# Audio.net
KiCad netlist of a schematic drawn in Altium Designer
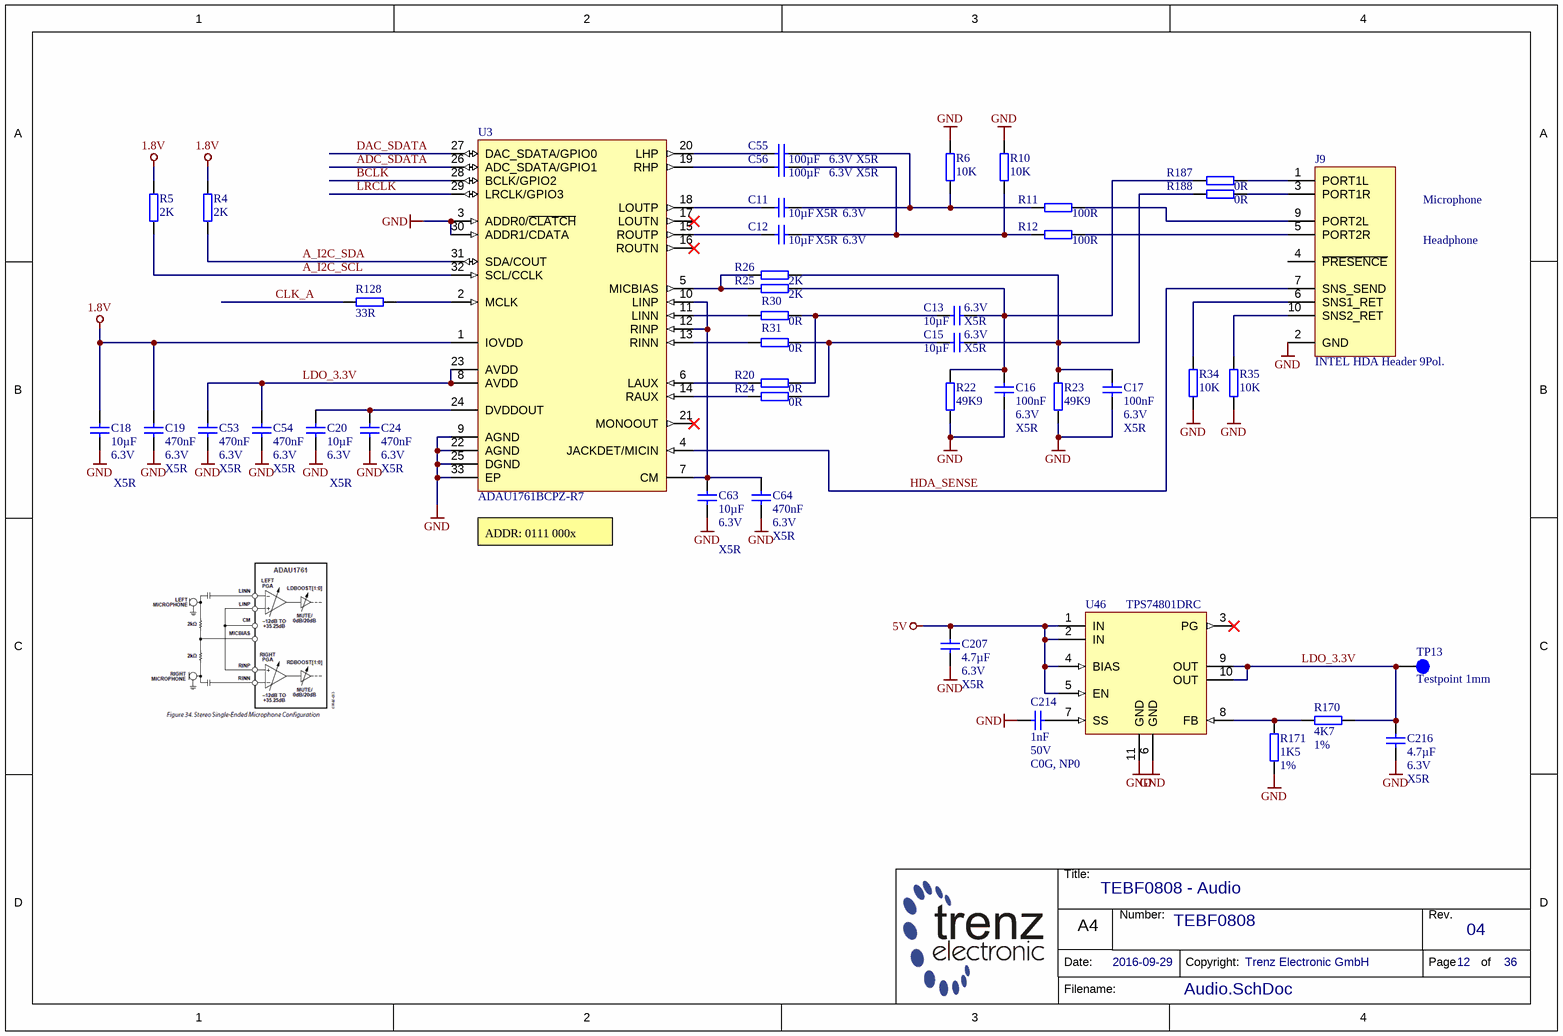
[diagram p0: Audio.SchDoc]

(export (version "E")
  (design (tool "Eeschema 10.0.6"))
  (components
    (comp (ref "C11")
      (value "10µF")
      (footprint "CAPC1608X90N")
      (description "KON 10µF 6,3V X5R SMD")
      (fields (field (name "VOLTAGE") "6.3V") (field (name "TECHNOLOGY") "X5R"))
      (libsource (lib "TE") (part "CAP-NP"))
    )
    (comp (ref "C12")
      (value "10µF")
      (footprint "CAPC1608X90N")
      (description "KON 10µF 6,3V X5R SMD")
      (fields (field (name "VOLTAGE") "6.3V") (field (name "TECHNOLOGY") "X5R"))
      (libsource (lib "TE") (part "CAP-NP"))
    )
    (comp (ref "C13")
      (value "10µF")
      (footprint "CAPC1608X90N")
      (description "KON 10µF 6,3V X5R SMD")
      (fields (field (name "VOLTAGE") "6.3V") (field (name "TECHNOLOGY") "X5R"))
      (libsource (lib "TE") (part "CAP-NP"))
    )
    (comp (ref "C15")
      (value "10µF")
      (footprint "CAPC1608X90N")
      (description "KON 10µF 6,3V X5R SMD")
      (fields (field (name "VOLTAGE") "6.3V") (field (name "TECHNOLOGY") "X5R"))
      (libsource (lib "TE") (part "CAP-NP"))
    )
    (comp (ref "C16")
      (value "100nF")
      (footprint "CAPC0603X33N")
      (description "KON 100nF 6.3V X5R SMD 10%")
      (fields
        (field (name "VOLTAGE") "6.3V")
        (field (name "TECHNOLOGY") "X5R")
        (field (name "TOLERANCE") "10%")
      )
      (libsource (lib "TE") (part "CAP-NP"))
    )
    (comp (ref "C17")
      (value "100nF")
      (footprint "CAPC0603X33N")
      (description "KON 100nF 6.3V X5R SMD 10%")
      (fields
        (field (name "VOLTAGE") "6.3V")
        (field (name "TECHNOLOGY") "X5R")
        (field (name "TOLERANCE") "10%")
      )
      (libsource (lib "TE") (part "CAP-NP"))
    )
    (comp (ref "C18")
      (value "10µF")
      (footprint "CAPC1608X90N")
      (description "KON 10µF 6,3V X5R SMD")
      (fields (field (name "VOLTAGE") "6.3V") (field (name "TECHNOLOGY") "X5R"))
      (libsource (lib "TE") (part "CAP-NP"))
    )
    (comp (ref "C19")
      (value "470nF")
      (footprint "CAPC1005X55N")
      (description "KON 470nF 6,3V X5R SMD")
      (fields (field (name "VOLTAGE") "6.3V") (field (name "TECHNOLOGY") "X5R"))
      (libsource (lib "TE") (part "CAP-NP"))
    )
    (comp (ref "C20")
      (value "10µF")
      (footprint "CAPC1608X90N")
      (description "KON 10µF 6,3V X5R SMD")
      (fields (field (name "VOLTAGE") "6.3V") (field (name "TECHNOLOGY") "X5R"))
      (libsource (lib "TE") (part "CAP-NP"))
    )
    (comp (ref "C24")
      (value "470nF")
      (footprint "CAPC1005X55N")
      (description "KON 470nF 6,3V X5R SMD")
      (fields (field (name "VOLTAGE") "6.3V") (field (name "TECHNOLOGY") "X5R"))
      (libsource (lib "TE") (part "CAP-NP"))
    )
    (comp (ref "C53")
      (value "470nF")
      (footprint "CAPC1005X55N")
      (description "KON 470nF 6,3V X5R SMD")
      (fields (field (name "VOLTAGE") "6.3V") (field (name "TECHNOLOGY") "X5R"))
      (libsource (lib "TE") (part "CAP-NP"))
    )
    (comp (ref "C54")
      (value "470nF")
      (footprint "CAPC1005X55N")
      (description "KON 470nF 6,3V X5R SMD")
      (fields (field (name "VOLTAGE") "6.3V") (field (name "TECHNOLOGY") "X5R"))
      (libsource (lib "TE") (part "CAP-NP"))
    )
    (comp (ref "C55")
      (value "100µF")
      (footprint "CAPC3216X180N")
      (description "KON 100µF 6,3V X5R SMD 20%")
      (fields
        (field (name "VOLTAGE") "6.3V")
        (field (name "TECHNOLOGY") "X5R")
        (field (name "TOLERANCE") "20%")
      )
      (libsource (lib "TE") (part "CAP-NP"))
    )
    (comp (ref "C56")
      (value "100µF")
      (footprint "CAPC3216X180N")
      (description "KON 100µF 6,3V X5R SMD 20%")
      (fields
        (field (name "VOLTAGE") "6.3V")
        (field (name "TECHNOLOGY") "X5R")
        (field (name "TOLERANCE") "20%")
      )
      (libsource (lib "TE") (part "CAP-NP"))
    )
    (comp (ref "C63")
      (value "10µF")
      (footprint "CAPC1608X90N")
      (description "KON 10µF 6,3V X5R SMD")
      (fields (field (name "VOLTAGE") "6.3V") (field (name "TECHNOLOGY") "X5R"))
      (libsource (lib "TE") (part "CAP-NP"))
    )
    (comp (ref "C64")
      (value "470nF")
      (footprint "CAPC1005X55N")
      (description "KON 470nF 6,3V X5R SMD")
      (fields (field (name "VOLTAGE") "6.3V") (field (name "TECHNOLOGY") "X5R"))
      (libsource (lib "TE") (part "CAP-NP"))
    )
    (comp (ref "C207")
      (value "4.7µF")
      (footprint "CAPC1005X60N")
      (description "KON 4.7µF 6.3V X5R SMD 20%")
      (fields
        (field (name "VOLTAGE") "6.3V")
        (field (name "TECHNOLOGY") "X5R")
        (field (name "TOLERANCE") "20%")
      )
      (libsource (lib "TE") (part "CAP-NP"))
    )
    (comp (ref "C214")
      (value "1nF")
      (footprint "CAPC1005X55N")
      (description "KON 1nF NP0 SMD 5%")
      (fields
        (field (name "VOLTAGE") "50V")
        (field (name "TECHNOLOGY") "C0G, NP0")
        (field (name "TOLERANCE") "5%")
      )
      (libsource (lib "TE") (part "CAP-NP"))
    )
    (comp (ref "C216")
      (value "4.7µF")
      (footprint "CAPC1005X60N")
      (description "KON 4.7µF 6.3V X5R SMD 20%")
      (fields
        (field (name "VOLTAGE") "6.3V")
        (field (name "TECHNOLOGY") "X5R")
        (field (name "TOLERANCE") "20%")
      )
      (libsource (lib "TE") (part "CAP-NP"))
    )
    (comp (ref "J9")
      (value "INTEL HDA Header 9Pol.")
      (footprint "INTEL_FP_HDA_9PIN")
      (description "Stiftleiste Intel HDA Header 9polig")
      (libsource (lib "TE") (part "INTEL_FP_HDA_9PIN"))
    )
    (comp (ref "R4")
      (value "2K")
      (footprint "RESC1005X40N")
      (description "WID SMD 2K 1% 0,063W")
      (fields (field (name "TOLERANCE") "1%"))
      (libsource (lib "TE") (part "RES"))
    )
    (comp (ref "R5")
      (value "2K")
      (footprint "RESC1005X40N")
      (description "WID SMD 2K 1% 0,063W")
      (fields (field (name "TOLERANCE") "1%"))
      (libsource (lib "TE") (part "RES"))
    )
    (comp (ref "R6")
      (value "10K")
      (footprint "RESC1005X40N")
      (description "WID SMD 10K 1% 0,063W")
      (fields (field (name "TOLERANCE") "1%"))
      (libsource (lib "TE") (part "RES"))
    )
    (comp (ref "R10")
      (value "10K")
      (footprint "RESC1005X40N")
      (description "WID SMD 10K 1% 0,063W")
      (fields (field (name "TOLERANCE") "1%"))
      (libsource (lib "TE") (part "RES"))
    )
    (comp (ref "R11")
      (value "100R")
      (footprint "RESC1005X40N")
      (description "WID SMD 100R 1% 0,063W")
      (fields (field (name "TOLERANCE") "1%"))
      (libsource (lib "TE") (part "RES"))
    )
    (comp (ref "R12")
      (value "100R")
      (footprint "RESC1005X40N")
      (description "WID SMD 100R 1% 0,063W")
      (fields (field (name "TOLERANCE") "1%"))
      (libsource (lib "TE") (part "RES"))
    )
    (comp (ref "R20")
      (value "0R")
      (footprint "RESC1005X40N")
      (description "WID SMD 0R")
      (fields (field (name "TOLERANCE") "1%"))
      (libsource (lib "TE") (part "RES"))
    )
    (comp (ref "R22")
      (value "49K9")
      (footprint "RESC1005X40N")
      (description "WID SMD 49K9 1% 0,063W")
      (fields (field (name "TOLERANCE") "1%"))
      (libsource (lib "TE") (part "RES"))
    )
    (comp (ref "R23")
      (value "49K9")
      (footprint "RESC1005X40N")
      (description "WID SMD 49K9 1% 0,063W")
      (fields (field (name "TOLERANCE") "1%"))
      (libsource (lib "TE") (part "RES"))
    )
    (comp (ref "R24")
      (value "0R")
      (footprint "RESC1005X40N")
      (description "WID SMD 0R")
      (fields (field (name "TOLERANCE") "1%"))
      (libsource (lib "TE") (part "RES"))
    )
    (comp (ref "R25")
      (value "2K")
      (footprint "RESC1005X40N")
      (description "WID SMD 2K 1% 0,063W")
      (fields (field (name "TOLERANCE") "1%"))
      (libsource (lib "TE") (part "RES"))
    )
    (comp (ref "R26")
      (value "2K")
      (footprint "RESC1005X40N")
      (description "WID SMD 2K 1% 0,063W")
      (fields (field (name "TOLERANCE") "1%"))
      (libsource (lib "TE") (part "RES"))
    )
    (comp (ref "R30")
      (value "0R")
      (footprint "RESC1005X40N")
      (description "WID SMD 0R")
      (fields (field (name "TOLERANCE") "1%"))
      (libsource (lib "TE") (part "RES"))
    )
    (comp (ref "R31")
      (value "0R")
      (footprint "RESC1005X40N")
      (description "WID SMD 0R")
      (fields (field (name "TOLERANCE") "1%"))
      (libsource (lib "TE") (part "RES"))
    )
    (comp (ref "R34")
      (value "10K")
      (footprint "RESC1005X40N")
      (description "WID SMD 10K 1% 0,063W")
      (fields (field (name "TOLERANCE") "1%"))
      (libsource (lib "TE") (part "RES"))
    )
    (comp (ref "R35")
      (value "10K")
      (footprint "RESC1005X40N")
      (description "WID SMD 10K 1% 0,063W")
      (fields (field (name "TOLERANCE") "1%"))
      (libsource (lib "TE") (part "RES"))
    )
    (comp (ref "R128")
      (value "33R")
      (footprint "RESC1005X40N")
      (description "WID SMD 33R 1% 0,063W")
      (fields (field (name "TOLERANCE") "1%"))
      (libsource (lib "TE") (part "RES"))
    )
    (comp (ref "R170")
      (value "4K7")
      (footprint "RESC1005X40N")
      (description "WID SMD 4K7 1% 0,063W")
      (fields (field (name "TOLERANCE") "1%"))
      (libsource (lib "TE") (part "RES"))
    )
    (comp (ref "R171")
      (value "1K5")
      (footprint "RESC1005X40N")
      (description "WID SMD 1K5 1% 0,063W")
      (fields (field (name "TOLERANCE") "1%"))
      (libsource (lib "TE") (part "RES"))
    )
    (comp (ref "R187")
      (value "0R")
      (footprint "RESC1005X40N")
      (description "WID SMD 0R")
      (fields (field (name "TOLERANCE") "1%"))
      (libsource (lib "TE") (part "RES"))
    )
    (comp (ref "R188")
      (value "0R")
      (footprint "RESC1005X40N")
      (description "WID SMD 0R")
      (fields (field (name "TOLERANCE") "1%"))
      (libsource (lib "TE") (part "RES"))
    )
    (comp (ref "TP13") (value "Testpoint 1mm") (footprint "TP_1mm") (libsource (lib "TE") (part "TP")))
    (comp (ref "U3")
      (value "ADAU1761BCPZ-R7")
      (footprint "QFN50P500X500X100-33N")
      (libsource (lib "TE") (part "ADAU1761BCPZ"))
    )
    (comp (ref "U46")
      (value "TPS74801DRC")
      (footprint "SON50P300X300X100-11N-TI")
      (libsource (lib "TE") (part "TPS74801DRC"))
    )
  )
  (nets
    (net (code "1") (name "/ADC_SDATA") (class "Default")
      (node (ref "U3") (pin "26") (pinfunction "ADC_SDATA/GPIO1_26") (pintype "bidirectional"))
    )
    (net (code "2") (name "/A_I2C_SCL") (class "Default")
      (node (ref "R5") (pin "1") (pinfunction "1_1") (pintype "passive"))
      (node (ref "U3") (pin "32") (pinfunction "SCL/CCLK_32") (pintype "input"))
    )
    (net (code "3") (name "/A_I2C_SDA") (class "Default")
      (node (ref "R4") (pin "1") (pinfunction "1_1") (pintype "passive"))
      (node (ref "U3") (pin "31") (pinfunction "SDA/COUT_31") (pintype "bidirectional"))
    )
    (net (code "4") (name "/BCLK") (class "Default")
      (node (ref "U3") (pin "28") (pinfunction "BCLK/GPIO2_28") (pintype "bidirectional"))
    )
    (net (code "5") (name "/CLK_A") (class "Default")
      (node (ref "R128") (pin "1") (pinfunction "1_1") (pintype "passive"))
    )
    (net (code "6") (name "/DAC_SDATA") (class "Default")
      (node (ref "U3") (pin "27") (pinfunction "DAC_SDATA/GPIO0_27") (pintype "bidirectional"))
    )
    (net (code "7") (name "/HDA_SENSE") (class "Default")
      (node (ref "J9") (pin "7") (pinfunction "SNS_SEND_7") (pintype "passive"))
      (node (ref "U3") (pin "4") (pinfunction "JACKDET/MICIN_4") (pintype "input"))
    )
    (net (code "8") (name "/LDO_3.3V") (class "Default")
      (node (ref "C216") (pin "1") (pinfunction "1_1") (pintype "passive"))
      (node (ref "C53") (pin "1") (pinfunction "1_1") (pintype "passive"))
      (node (ref "C54") (pin "1") (pinfunction "1_1") (pintype "passive"))
      (node (ref "R170") (pin "2") (pinfunction "2_2") (pintype "passive"))
      (node (ref "TP13") (pin "1") (pintype "passive"))
      (node (ref "U3") (pin "23") (pinfunction "AVDD_23") (pintype "power_in"))
      (node (ref "U3") (pin "8") (pinfunction "AVDD_8") (pintype "power_in"))
      (node (ref "U46") (pin "10") (pinfunction "OUT_10") (pintype "power_in"))
      (node (ref "U46") (pin "9") (pinfunction "OUT_9") (pintype "power_in"))
    )
    (net (code "9") (name "/LRCLK") (class "Default")
      (node (ref "U3") (pin "29") (pinfunction "LRCLK/GPIO3_29") (pintype "bidirectional"))
    )
    (net (code "10") (name "1.8V") (class "Default")
      (node (ref "C18") (pin "1") (pinfunction "1_1") (pintype "passive"))
      (node (ref "C19") (pin "1") (pinfunction "1_1") (pintype "passive"))
      (node (ref "R4") (pin "2") (pinfunction "2_2") (pintype "passive"))
      (node (ref "R5") (pin "2") (pinfunction "2_2") (pintype "passive"))
      (node (ref "U3") (pin "1") (pinfunction "IOVDD_1") (pintype "power_in"))
    )
    (net (code "11") (name "5V") (class "Default")
      (node (ref "C207") (pin "1") (pinfunction "1_1") (pintype "passive"))
      (node (ref "U46") (pin "1") (pinfunction "IN_1") (pintype "power_in"))
      (node (ref "U46") (pin "2") (pinfunction "IN_2") (pintype "power_in"))
      (node (ref "U46") (pin "4") (pinfunction "BIAS_4") (pintype "input"))
      (node (ref "U46") (pin "5") (pinfunction "EN_5") (pintype "input"))
    )
    (net (code "12") (name "GND") (class "Default")
      (node (ref "C16") (pin "1") (pinfunction "1_1") (pintype "passive"))
      (node (ref "C17") (pin "1") (pinfunction "1_1") (pintype "passive"))
      (node (ref "C18") (pin "2") (pinfunction "2_2") (pintype "passive"))
      (node (ref "C19") (pin "2") (pinfunction "2_2") (pintype "passive"))
      (node (ref "C20") (pin "2") (pinfunction "2_2") (pintype "passive"))
      (node (ref "C207") (pin "2") (pinfunction "2_2") (pintype "passive"))
      (node (ref "C214") (pin "1") (pinfunction "1_1") (pintype "passive"))
      (node (ref "C216") (pin "2") (pinfunction "2_2") (pintype "passive"))
      (node (ref "C24") (pin "2") (pinfunction "2_2") (pintype "passive"))
      (node (ref "C53") (pin "2") (pinfunction "2_2") (pintype "passive"))
      (node (ref "C54") (pin "2") (pinfunction "2_2") (pintype "passive"))
      (node (ref "C63") (pin "2") (pinfunction "2_2") (pintype "passive"))
      (node (ref "C64") (pin "2") (pinfunction "2_2") (pintype "passive"))
      (node (ref "J9") (pin "2") (pinfunction "GND_2") (pintype "passive"))
      (node (ref "R10") (pin "1") (pinfunction "1_1") (pintype "passive"))
      (node (ref "R171") (pin "2") (pinfunction "2_2") (pintype "passive"))
      (node (ref "R22") (pin "2") (pinfunction "2_2") (pintype "passive"))
      (node (ref "R23") (pin "2") (pinfunction "2_2") (pintype "passive"))
      (node (ref "R34") (pin "1") (pinfunction "1_1") (pintype "passive"))
      (node (ref "R35") (pin "1") (pinfunction "1_1") (pintype "passive"))
      (node (ref "R6") (pin "1") (pinfunction "1_1") (pintype "passive"))
      (node (ref "U3") (pin "22") (pinfunction "AGND_22") (pintype "power_in"))
      (node (ref "U3") (pin "25") (pinfunction "DGND_25") (pintype "power_in"))
      (node (ref "U3") (pin "3") (pinfunction "ADDR0/~{CLATCH}_3") (pintype "input"))
      (node (ref "U3") (pin "30") (pinfunction "ADDR1/CDATA_30") (pintype "input"))
      (node (ref "U3") (pin "33") (pinfunction "EP_33") (pintype "power_in"))
      (node (ref "U3") (pin "9") (pinfunction "AGND_9") (pintype "power_in"))
      (node (ref "U46") (pin "11") (pinfunction "GND_11") (pintype "power_in"))
      (node (ref "U46") (pin "6") (pinfunction "GND_6") (pintype "power_in"))
    )
    (net (code "13") (name "Net-(C11-Pad2)") (class "Default")
      (node (ref "C11") (pin "2") (pinfunction "2_2") (pintype "passive"))
      (node (ref "C55") (pin "2") (pinfunction "2_2") (pintype "passive"))
      (node (ref "R11") (pin "1") (pinfunction "1_1") (pintype "passive"))
      (node (ref "R6") (pin "2") (pinfunction "2_2") (pintype "passive"))
    )
    (net (code "14") (name "Net-(C12-Pad2)") (class "Default")
      (node (ref "C12") (pin "2") (pinfunction "2_2") (pintype "passive"))
      (node (ref "C56") (pin "2") (pinfunction "2_2") (pintype "passive"))
      (node (ref "R10") (pin "2") (pinfunction "2_2") (pintype "passive"))
      (node (ref "R12") (pin "1") (pinfunction "1_1") (pintype "passive"))
    )
    (net (code "15") (name "Net-(C13-Pad1)") (class "Default")
      (node (ref "C13") (pin "1") (pinfunction "1_1") (pintype "passive"))
      (node (ref "R20") (pin "1") (pinfunction "1_1") (pintype "passive"))
      (node (ref "R30") (pin "1") (pinfunction "1_1") (pintype "passive"))
    )
    (net (code "16") (name "Net-(C13-Pad2)") (class "Default")
      (node (ref "C13") (pin "2") (pinfunction "2_2") (pintype "passive"))
      (node (ref "C16") (pin "2") (pinfunction "2_2") (pintype "passive"))
      (node (ref "R187") (pin "2") (pinfunction "2_2") (pintype "passive"))
      (node (ref "R22") (pin "1") (pinfunction "1_1") (pintype "passive"))
      (node (ref "R25") (pin "2") (pinfunction "2_2") (pintype "passive"))
    )
    (net (code "17") (name "Net-(C15-Pad1)") (class "Default")
      (node (ref "C15") (pin "1") (pinfunction "1_1") (pintype "passive"))
      (node (ref "R24") (pin "1") (pinfunction "1_1") (pintype "passive"))
      (node (ref "R31") (pin "1") (pinfunction "1_1") (pintype "passive"))
    )
    (net (code "18") (name "Net-(C15-Pad2)") (class "Default")
      (node (ref "C15") (pin "2") (pinfunction "2_2") (pintype "passive"))
      (node (ref "C17") (pin "2") (pinfunction "2_2") (pintype "passive"))
      (node (ref "R188") (pin "2") (pinfunction "2_2") (pintype "passive"))
      (node (ref "R23") (pin "1") (pinfunction "1_1") (pintype "passive"))
      (node (ref "R26") (pin "2") (pinfunction "2_2") (pintype "passive"))
    )
    (net (code "19") (name "Net-(J9-PORT1L)") (class "Default")
      (node (ref "J9") (pin "1") (pinfunction "PORT1L_1") (pintype "passive"))
      (node (ref "R187") (pin "1") (pinfunction "1_1") (pintype "passive"))
    )
    (net (code "20") (name "Net-(J9-PORT1R)") (class "Default")
      (node (ref "J9") (pin "3") (pinfunction "PORT1R_3") (pintype "passive"))
      (node (ref "R188") (pin "1") (pinfunction "1_1") (pintype "passive"))
    )
    (net (code "21") (name "Net-(J9-PORT2L)") (class "Default")
      (node (ref "J9") (pin "9") (pinfunction "PORT2L_9") (pintype "passive"))
      (node (ref "R11") (pin "2") (pinfunction "2_2") (pintype "passive"))
    )
    (net (code "22") (name "Net-(J9-PORT2R)") (class "Default")
      (node (ref "J9") (pin "5") (pinfunction "PORT2R_5") (pintype "passive"))
      (node (ref "R12") (pin "2") (pinfunction "2_2") (pintype "passive"))
    )
    (net (code "23") (name "Net-(J9-SNS1_RET)") (class "Default")
      (node (ref "J9") (pin "6") (pinfunction "SNS1_RET_6") (pintype "passive"))
      (node (ref "R34") (pin "2") (pinfunction "2_2") (pintype "passive"))
    )
    (net (code "24") (name "Net-(J9-SNS2_RET)") (class "Default")
      (node (ref "J9") (pin "10") (pinfunction "SNS2_RET_10") (pintype "passive"))
      (node (ref "R35") (pin "2") (pinfunction "2_2") (pintype "passive"))
    )
    (net (code "25") (name "Net-(U3-CM)") (class "Default")
      (node (ref "C63") (pin "1") (pinfunction "1_1") (pintype "passive"))
      (node (ref "C64") (pin "1") (pinfunction "1_1") (pintype "passive"))
      (node (ref "U3") (pin "10") (pinfunction "LINP_10") (pintype "input"))
      (node (ref "U3") (pin "12") (pinfunction "RINP_12") (pintype "input"))
      (node (ref "U3") (pin "7") (pinfunction "CM_7") (pintype "passive"))
    )
    (net (code "26") (name "Net-(U3-DVDDOUT)") (class "Default")
      (node (ref "C20") (pin "1") (pinfunction "1_1") (pintype "passive"))
      (node (ref "C24") (pin "1") (pinfunction "1_1") (pintype "passive"))
      (node (ref "U3") (pin "24") (pinfunction "DVDDOUT_24") (pintype "power_in"))
    )
    (net (code "27") (name "Net-(U3-LAUX)") (class "Default")
      (node (ref "R20") (pin "2") (pinfunction "2_2") (pintype "passive"))
      (node (ref "U3") (pin "6") (pinfunction "LAUX_6") (pintype "input"))
    )
    (net (code "28") (name "Net-(U3-LHP)") (class "Default")
      (node (ref "C55") (pin "1") (pinfunction "1_1") (pintype "passive"))
      (node (ref "U3") (pin "20") (pinfunction "LHP_20") (pintype "output"))
    )
    (net (code "29") (name "Net-(U3-LINN)") (class "Default")
      (node (ref "R30") (pin "2") (pinfunction "2_2") (pintype "passive"))
      (node (ref "U3") (pin "11") (pinfunction "LINN_11") (pintype "input"))
    )
    (net (code "30") (name "Net-(U3-LOUTP)") (class "Default")
      (node (ref "C11") (pin "1") (pinfunction "1_1") (pintype "passive"))
      (node (ref "U3") (pin "18") (pinfunction "LOUTP_18") (pintype "output"))
    )
    (net (code "31") (name "Net-(U3-MCLK)") (class "Default")
      (node (ref "R128") (pin "2") (pinfunction "2_2") (pintype "passive"))
      (node (ref "U3") (pin "2") (pinfunction "MCLK_2") (pintype "input"))
    )
    (net (code "32") (name "Net-(U3-MICBIAS)") (class "Default")
      (node (ref "R25") (pin "1") (pinfunction "1_1") (pintype "passive"))
      (node (ref "R26") (pin "1") (pinfunction "1_1") (pintype "passive"))
      (node (ref "U3") (pin "5") (pinfunction "MICBIAS_5") (pintype "output"))
    )
    (net (code "33") (name "Net-(U3-RAUX)") (class "Default")
      (node (ref "R24") (pin "2") (pinfunction "2_2") (pintype "passive"))
      (node (ref "U3") (pin "14") (pinfunction "RAUX_14") (pintype "input"))
    )
    (net (code "34") (name "Net-(U3-RHP)") (class "Default")
      (node (ref "C56") (pin "1") (pinfunction "1_1") (pintype "passive"))
      (node (ref "U3") (pin "19") (pinfunction "RHP_19") (pintype "output"))
    )
    (net (code "35") (name "Net-(U3-RINN)") (class "Default")
      (node (ref "R31") (pin "2") (pinfunction "2_2") (pintype "passive"))
      (node (ref "U3") (pin "13") (pinfunction "RINN_13") (pintype "input"))
    )
    (net (code "36") (name "Net-(U3-ROUTP)") (class "Default")
      (node (ref "C12") (pin "1") (pinfunction "1_1") (pintype "passive"))
      (node (ref "U3") (pin "15") (pinfunction "ROUTP_15") (pintype "output"))
    )
    (net (code "37") (name "Net-(U46-FB)") (class "Default")
      (node (ref "R170") (pin "1") (pinfunction "1_1") (pintype "passive"))
      (node (ref "R171") (pin "1") (pinfunction "1_1") (pintype "passive"))
      (node (ref "U46") (pin "8") (pinfunction "FB_8") (pintype "input"))
    )
    (net (code "38") (name "Net-(U46-SS)") (class "Default")
      (node (ref "C214") (pin "2") (pinfunction "2_2") (pintype "passive"))
      (node (ref "U46") (pin "7") (pinfunction "SS_7") (pintype "input"))
    )
    (net (code "39") (name "unconnected-(J9-~{PRESENCE}-Pad4)") (class "Default")
      (node (ref "J9") (pin "4") (pinfunction "~{PRESENCE}_4") (pintype "passive"))
    )
    (net (code "40") (name "unconnected-(U3-LOUTN-Pad17)") (class "Default")
      (node (ref "U3") (pin "17") (pinfunction "LOUTN_17") (pintype "output+no_connect"))
    )
    (net (code "41") (name "unconnected-(U3-MONOOUT-Pad21)") (class "Default")
      (node (ref "U3") (pin "21") (pinfunction "MONOOUT_21") (pintype "output+no_connect"))
    )
    (net (code "42") (name "unconnected-(U3-ROUTN-Pad16)") (class "Default")
      (node (ref "U3") (pin "16") (pinfunction "ROUTN_16") (pintype "output+no_connect"))
    )
    (net (code "43") (name "unconnected-(U46-PG-Pad3)") (class "Default")
      (node (ref "U46") (pin "3") (pinfunction "PG_3") (pintype "output+no_connect"))
    )
  )
)
